# qo-100-relay-controller.net
KiCad netlist of a schematic drawn in EAGLE
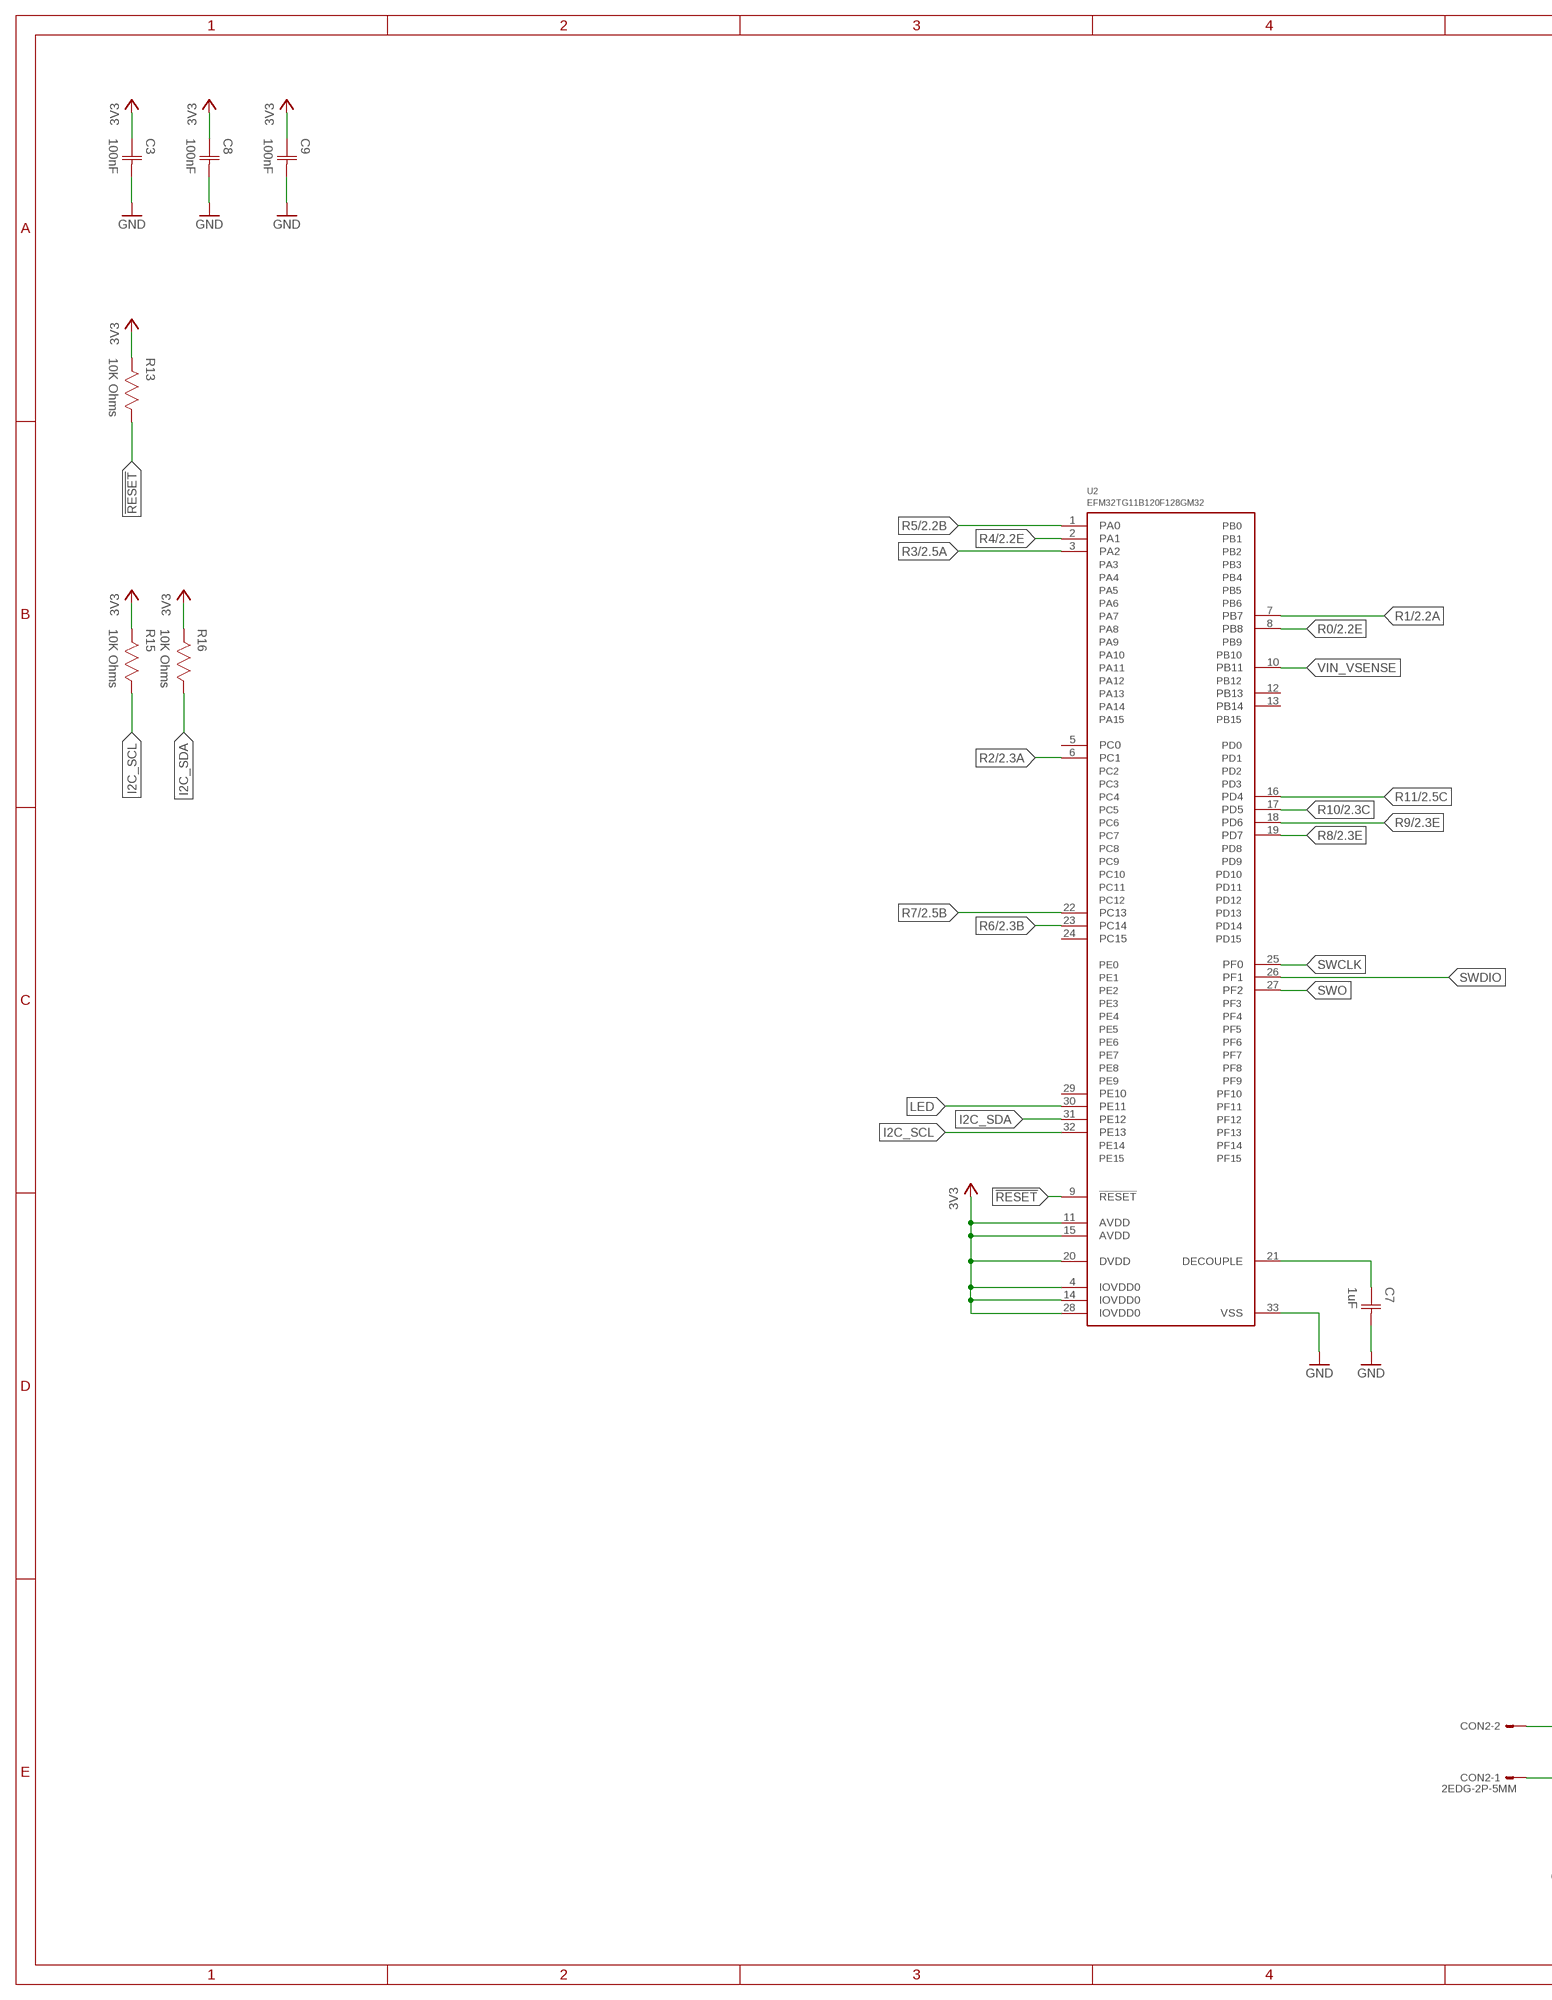
[diagram p0: schematic, sheet 1, part 1 of 2]
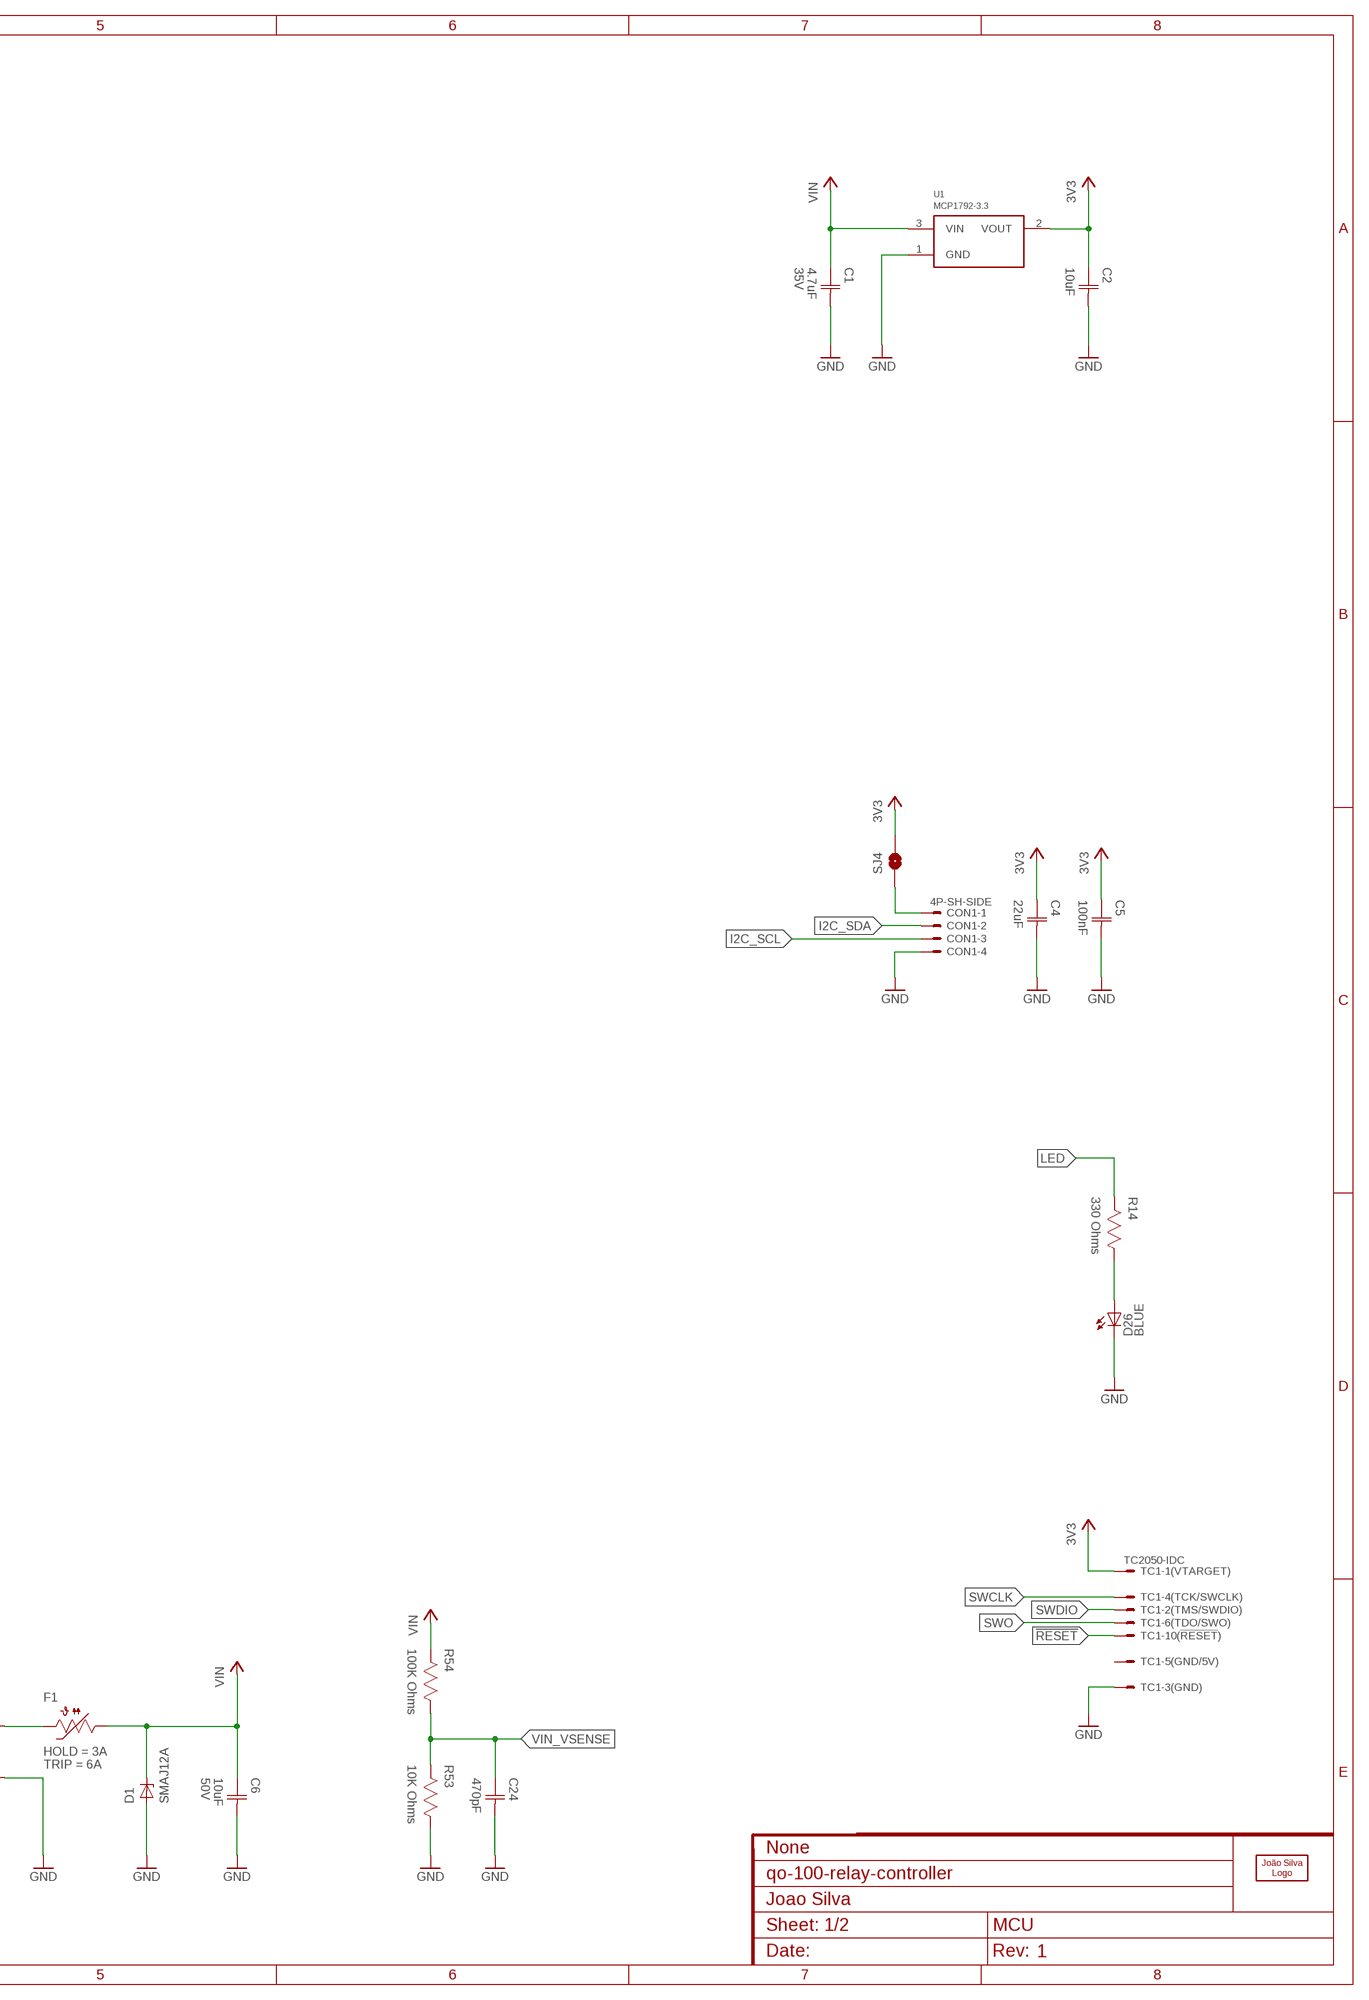
[diagram p1: schematic, sheet 1, part 2 of 2]
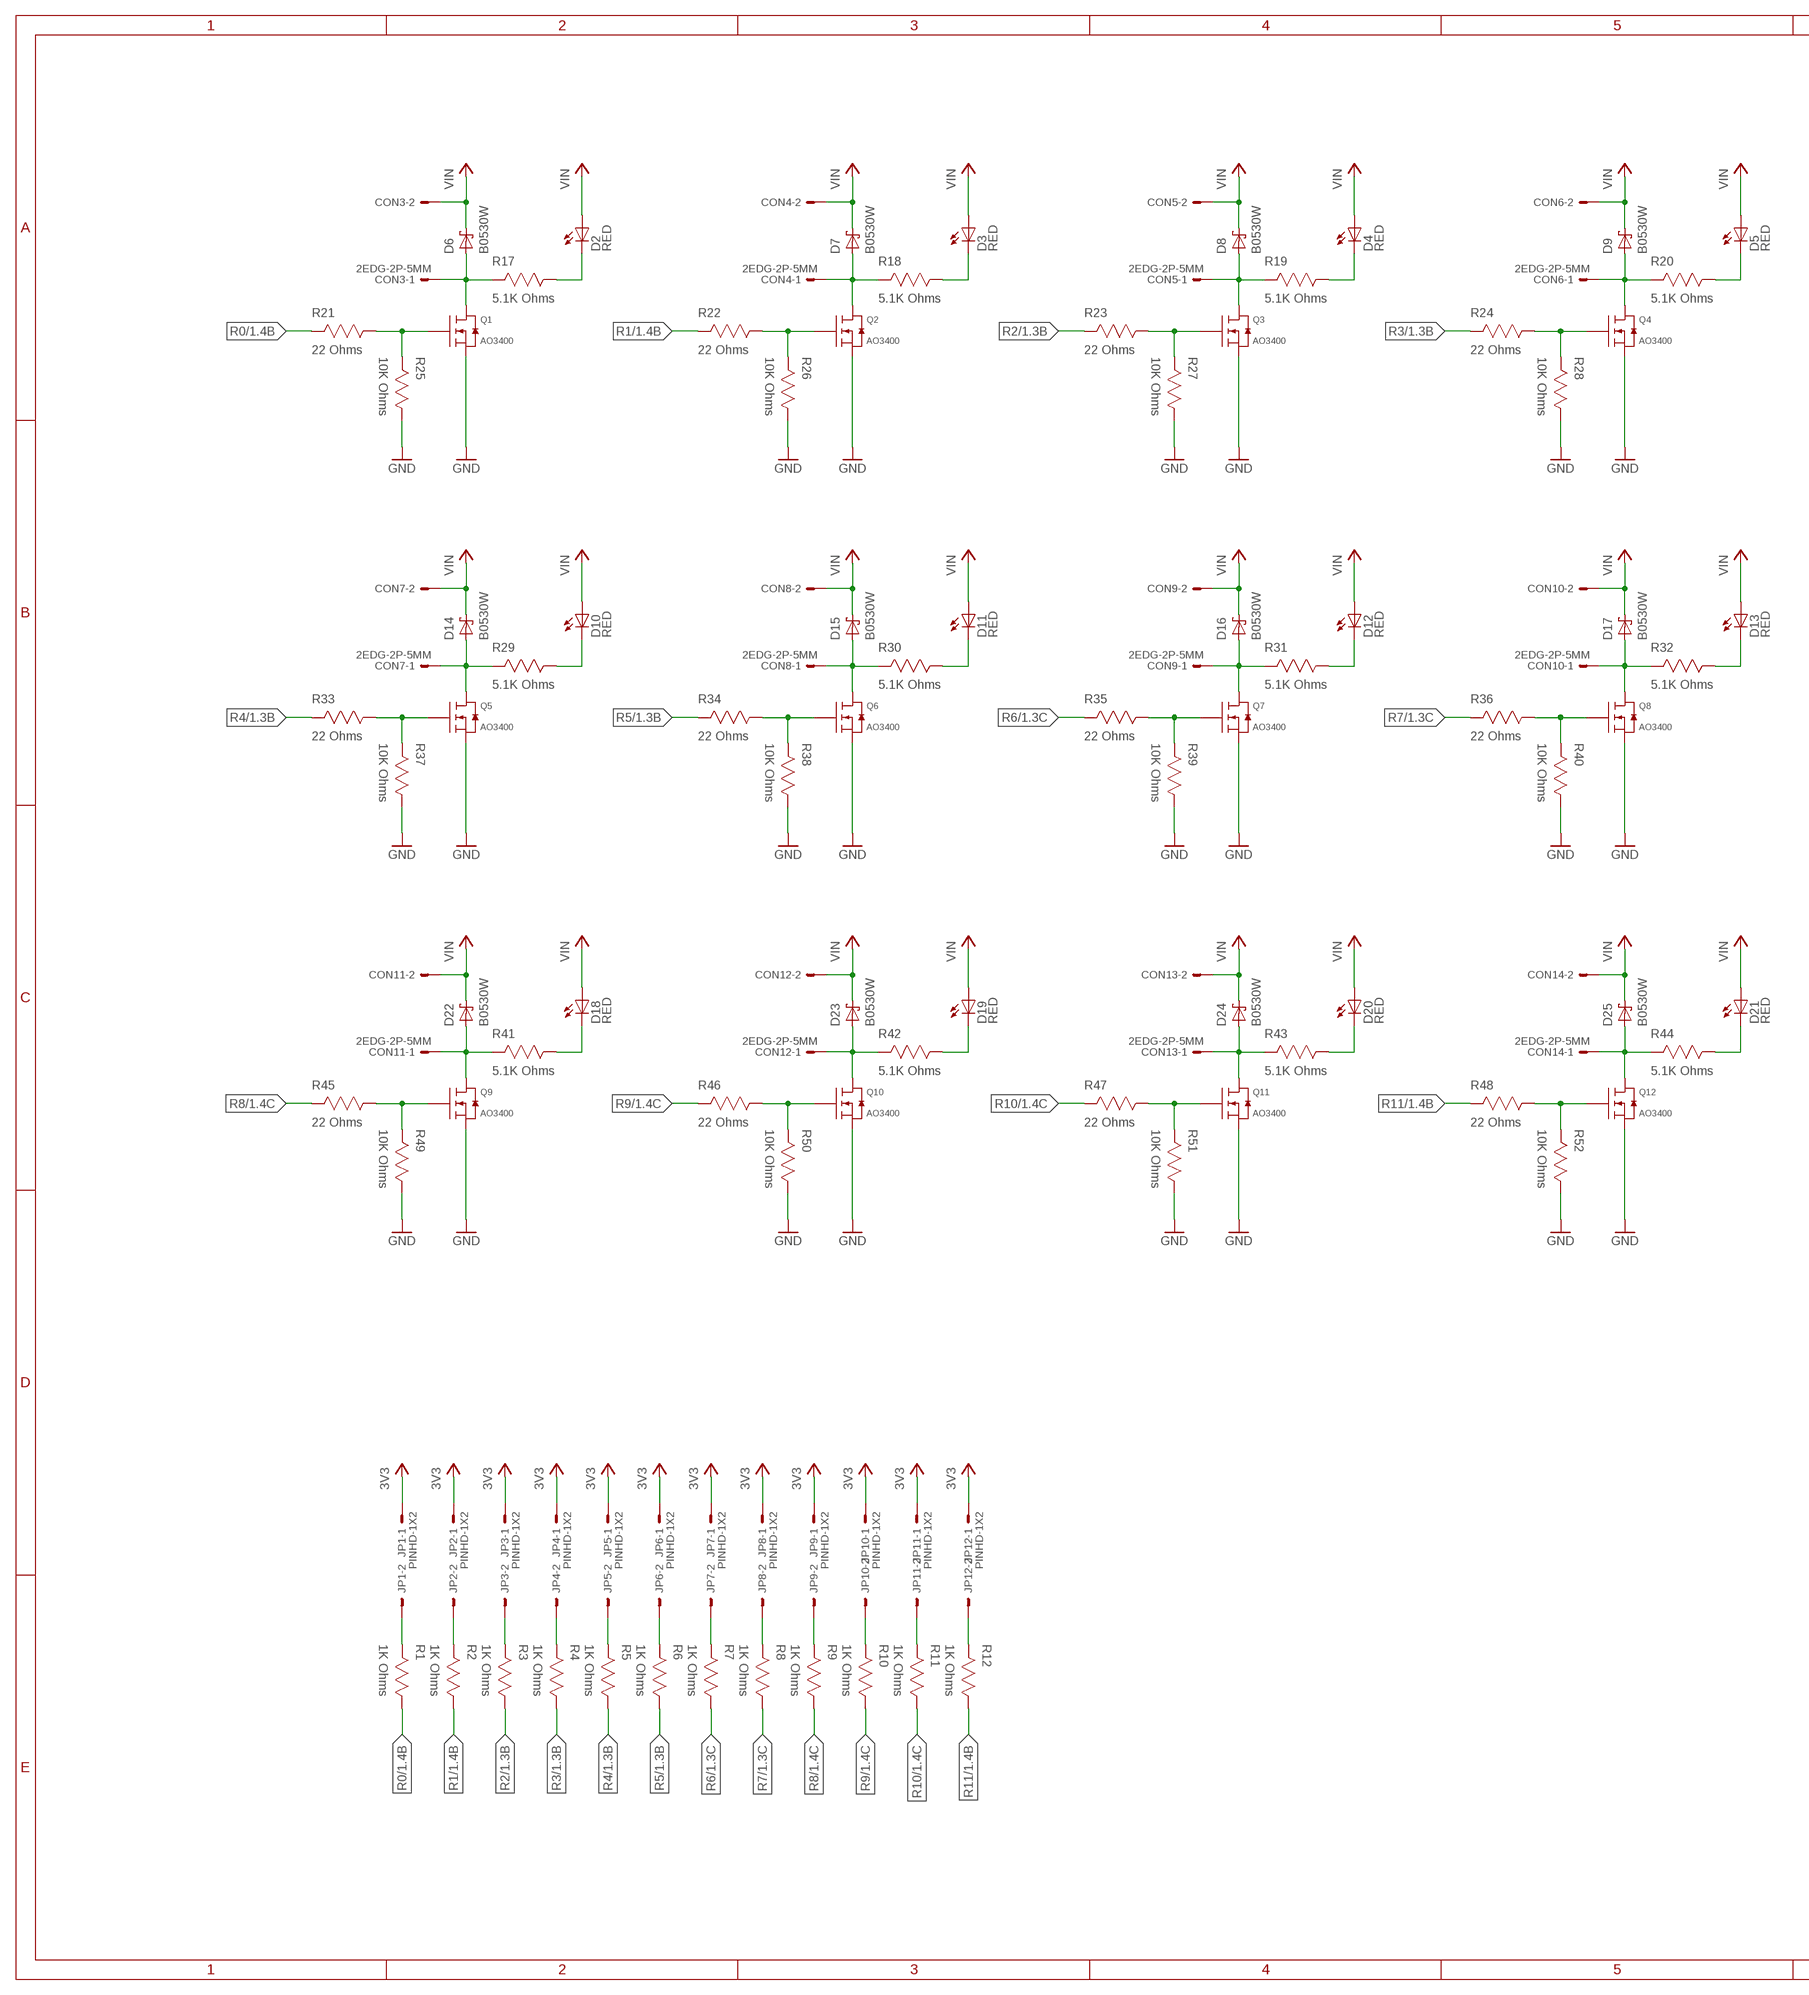
[diagram p2: schematic, sheet 2, part 1 of 2]
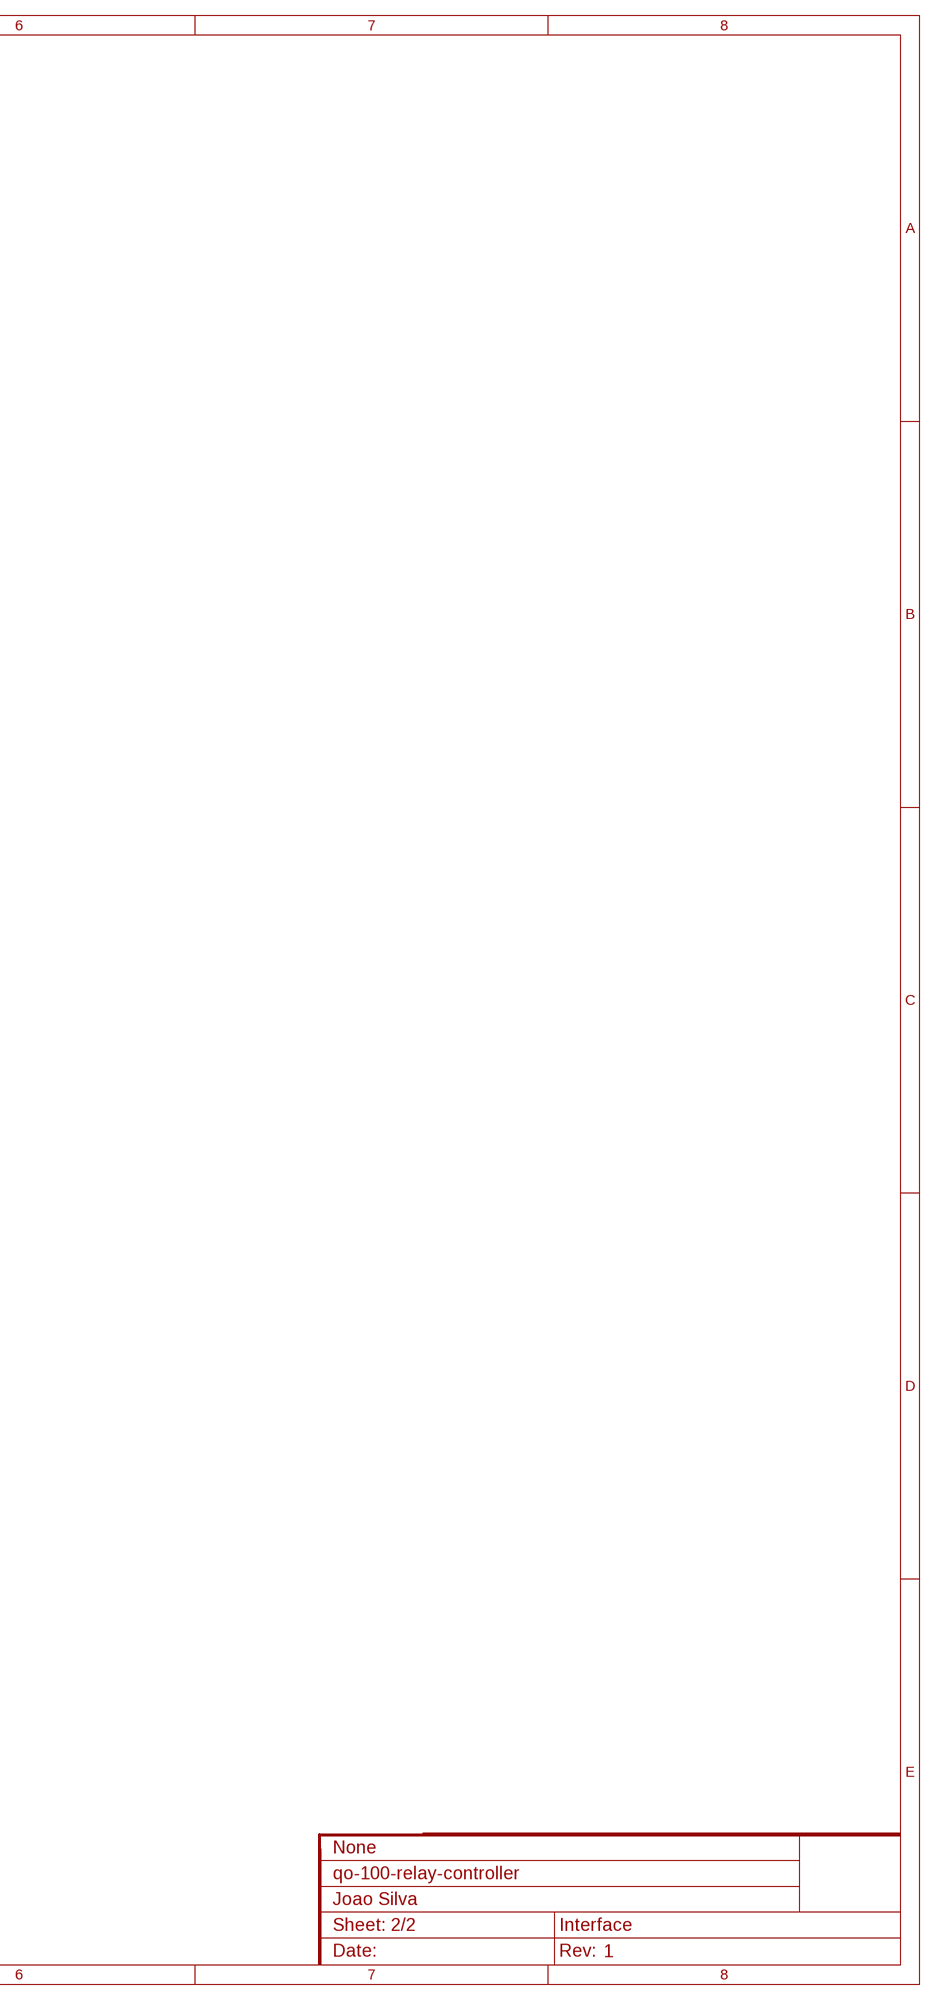
[diagram p3: schematic, sheet 2, part 2 of 2]

(export (version "E")
  (design (tool "Eeschema 10.0.6"))
  (components
    (comp (ref "C1")
      (value "4.7uF")
      (footprint "eagle-import:CAP0603")
      (fields (field (name "VOLTAGE") "35V"))
      (libsource (lib "eagle-import") (part "CAPACITOR-0603"))
    )
    (comp (ref "C2")
      (value "10uF")
      (footprint "eagle-import:CAP0603")
      (libsource (lib "eagle-import") (part "CAPACITOR-0603"))
    )
    (comp (ref "C3")
      (value "100nF")
      (footprint "eagle-import:CAP0603")
      (libsource (lib "eagle-import") (part "CAPACITOR-0603"))
    )
    (comp (ref "C4")
      (value "22uF")
      (footprint "eagle-import:CAP1206")
      (libsource (lib "eagle-import") (part "CAPACITOR-1206"))
    )
    (comp (ref "C5")
      (value "100nF")
      (footprint "eagle-import:CAP0603")
      (libsource (lib "eagle-import") (part "CAPACITOR-0603"))
    )
    (comp (ref "C6")
      (value "10uF")
      (footprint "eagle-import:CAP1206")
      (fields (field (name "VOLTAGE") "50V"))
      (libsource (lib "eagle-import") (part "CAPACITOR-1206"))
    )
    (comp (ref "C7")
      (value "1uF")
      (footprint "eagle-import:CAP0603")
      (libsource (lib "eagle-import") (part "CAPACITOR-0603"))
    )
    (comp (ref "C8")
      (value "100nF")
      (footprint "eagle-import:CAP0603")
      (libsource (lib "eagle-import") (part "CAPACITOR-0603"))
    )
    (comp (ref "C9")
      (value "100nF")
      (footprint "eagle-import:CAP0603")
      (libsource (lib "eagle-import") (part "CAPACITOR-0603"))
    )
    (comp (ref "C24")
      (value "470pF")
      (footprint "eagle-import:CAP0603")
      (libsource (lib "eagle-import") (part "CAPACITOR-0603"))
    )
    (comp (ref "CON1")
      (value "4P-SH-SIDE")
      (footprint "eagle-import:SH-04-SIDE")
      (libsource (lib "eagle-import") (part "4P-SH-SIDE"))
    )
    (comp (ref "CON2")
      (value "2EDG-2P-5MM")
      (footprint "eagle-import:2EDG-2P-5MM")
      (libsource (lib "eagle-import") (part "2EDG-2P-5MM"))
    )
    (comp (ref "D1")
      (value "SMAJ12A")
      (footprint "eagle-import:DO214AC")
      (fields (field (name "MF") "Littelfuse"))
      (libsource (lib "eagle-import") (part "SMAJA12"))
    )
    (comp (ref "D26")
      (value "LED0603")
      (footprint "eagle-import:0603")
      (fields (field (name "COLOR") "BLUE"))
      (libsource (lib "eagle-import") (part "LED0603"))
    )
    (comp (ref "F1")
      (value "2.6A Hold")
      (footprint "eagle-import:1206")
      (fields (field (name "HOLD") "3A") (field (name "TRIP") "6A"))
      (libsource (lib "eagle-import") (part "PTC1206"))
    )
    (comp (ref "LOGO1")
      (value "JS-5MM")
      (footprint "eagle-import:JS_5MM")
      (libsource (lib "eagle-import") (part "JS-5MM"))
    )
    (comp (ref "R13")
      (value "10K Ohms")
      (footprint "eagle-import:RES0603")
      (libsource (lib "eagle-import") (part "RESISTOR-0603"))
    )
    (comp (ref "R14")
      (value "330 Ohms")
      (footprint "eagle-import:RES0603")
      (libsource (lib "eagle-import") (part "RESISTOR-0603"))
    )
    (comp (ref "R15")
      (value "10K Ohms")
      (footprint "eagle-import:RES0603")
      (libsource (lib "eagle-import") (part "RESISTOR-0603"))
    )
    (comp (ref "R16")
      (value "10K Ohms")
      (footprint "eagle-import:RES0603")
      (libsource (lib "eagle-import") (part "RESISTOR-0603"))
    )
    (comp (ref "R53")
      (value "10K Ohms")
      (footprint "eagle-import:RES0603")
      (libsource (lib "eagle-import") (part "RESISTOR-0603"))
    )
    (comp (ref "R54")
      (value "100K Ohms")
      (footprint "eagle-import:RES0603")
      (libsource (lib "eagle-import") (part "RESISTOR-0603"))
    )
    (comp (ref "SJ4")
      (value "SJS")
      (footprint "eagle-import:SJ_S")
      (libsource (lib "eagle-import") (part "SJS"))
    )
    (comp (ref "TC1")
      (value "TC2050-IDC")
      (footprint "eagle-import:TC2050-IDC")
      (libsource (lib "eagle-import") (part "TC2050-IDC"))
    )
    (comp (ref "U1")
      (value "MCP1792-3.3")
      (footprint "eagle-import:SOT23")
      (libsource (lib "eagle-import") (part "MCP1792-3.3"))
    )
    (comp (ref "U2")
      (value "EFM32TG11B120F128GM32")
      (footprint "eagle-import:QFN32_0.5P_TG")
      (libsource (lib "eagle-import") (part "EFM32TG11B1M3220F128G"))
    )
    (comp (ref "CON3")
      (value "2EDG-2P-5MM")
      (footprint "eagle-import:2EDG-2P-5MM")
      (libsource (lib "eagle-import") (part "2EDG-2P-5MM"))
    )
    (comp (ref "CON4")
      (value "2EDG-2P-5MM")
      (footprint "eagle-import:2EDG-2P-5MM")
      (libsource (lib "eagle-import") (part "2EDG-2P-5MM"))
    )
    (comp (ref "CON5")
      (value "2EDG-2P-5MM")
      (footprint "eagle-import:2EDG-2P-5MM")
      (libsource (lib "eagle-import") (part "2EDG-2P-5MM"))
    )
    (comp (ref "CON6")
      (value "2EDG-2P-5MM")
      (footprint "eagle-import:2EDG-2P-5MM")
      (libsource (lib "eagle-import") (part "2EDG-2P-5MM"))
    )
    (comp (ref "CON7")
      (value "2EDG-2P-5MM")
      (footprint "eagle-import:2EDG-2P-5MM")
      (libsource (lib "eagle-import") (part "2EDG-2P-5MM"))
    )
    (comp (ref "CON8")
      (value "2EDG-2P-5MM")
      (footprint "eagle-import:2EDG-2P-5MM")
      (libsource (lib "eagle-import") (part "2EDG-2P-5MM"))
    )
    (comp (ref "CON9")
      (value "2EDG-2P-5MM")
      (footprint "eagle-import:2EDG-2P-5MM")
      (libsource (lib "eagle-import") (part "2EDG-2P-5MM"))
    )
    (comp (ref "CON10")
      (value "2EDG-2P-5MM")
      (footprint "eagle-import:2EDG-2P-5MM")
      (libsource (lib "eagle-import") (part "2EDG-2P-5MM"))
    )
    (comp (ref "CON11")
      (value "2EDG-2P-5MM")
      (footprint "eagle-import:2EDG-2P-5MM")
      (libsource (lib "eagle-import") (part "2EDG-2P-5MM"))
    )
    (comp (ref "CON12")
      (value "2EDG-2P-5MM")
      (footprint "eagle-import:2EDG-2P-5MM")
      (libsource (lib "eagle-import") (part "2EDG-2P-5MM"))
    )
    (comp (ref "CON13")
      (value "2EDG-2P-5MM")
      (footprint "eagle-import:2EDG-2P-5MM")
      (libsource (lib "eagle-import") (part "2EDG-2P-5MM"))
    )
    (comp (ref "CON14")
      (value "2EDG-2P-5MM")
      (footprint "eagle-import:2EDG-2P-5MM")
      (libsource (lib "eagle-import") (part "2EDG-2P-5MM"))
    )
    (comp (ref "D2")
      (value "LED0603")
      (footprint "eagle-import:0603")
      (fields (field (name "COLOR") "RED"))
      (libsource (lib "eagle-import") (part "LED0603"))
    )
    (comp (ref "D3")
      (value "LED0603")
      (footprint "eagle-import:0603")
      (fields (field (name "COLOR") "RED"))
      (libsource (lib "eagle-import") (part "LED0603"))
    )
    (comp (ref "D4")
      (value "LED0603")
      (footprint "eagle-import:0603")
      (fields (field (name "COLOR") "RED"))
      (libsource (lib "eagle-import") (part "LED0603"))
    )
    (comp (ref "D5")
      (value "LED0603")
      (footprint "eagle-import:0603")
      (fields (field (name "COLOR") "RED"))
      (libsource (lib "eagle-import") (part "LED0603"))
    )
    (comp (ref "D6")
      (value "B0530W")
      (footprint "eagle-import:SOD-123")
      (libsource (lib "eagle-import") (part "B0530W"))
    )
    (comp (ref "D7")
      (value "B0530W")
      (footprint "eagle-import:SOD-123")
      (libsource (lib "eagle-import") (part "B0530W"))
    )
    (comp (ref "D8")
      (value "B0530W")
      (footprint "eagle-import:SOD-123")
      (libsource (lib "eagle-import") (part "B0530W"))
    )
    (comp (ref "D9")
      (value "B0530W")
      (footprint "eagle-import:SOD-123")
      (libsource (lib "eagle-import") (part "B0530W"))
    )
    (comp (ref "D10")
      (value "LED0603")
      (footprint "eagle-import:0603")
      (fields (field (name "COLOR") "RED"))
      (libsource (lib "eagle-import") (part "LED0603"))
    )
    (comp (ref "D11")
      (value "LED0603")
      (footprint "eagle-import:0603")
      (fields (field (name "COLOR") "RED"))
      (libsource (lib "eagle-import") (part "LED0603"))
    )
    (comp (ref "D12")
      (value "LED0603")
      (footprint "eagle-import:0603")
      (fields (field (name "COLOR") "RED"))
      (libsource (lib "eagle-import") (part "LED0603"))
    )
    (comp (ref "D13")
      (value "LED0603")
      (footprint "eagle-import:0603")
      (fields (field (name "COLOR") "RED"))
      (libsource (lib "eagle-import") (part "LED0603"))
    )
    (comp (ref "D14")
      (value "B0530W")
      (footprint "eagle-import:SOD-123")
      (libsource (lib "eagle-import") (part "B0530W"))
    )
    (comp (ref "D15")
      (value "B0530W")
      (footprint "eagle-import:SOD-123")
      (libsource (lib "eagle-import") (part "B0530W"))
    )
    (comp (ref "D16")
      (value "B0530W")
      (footprint "eagle-import:SOD-123")
      (libsource (lib "eagle-import") (part "B0530W"))
    )
    (comp (ref "D17")
      (value "B0530W")
      (footprint "eagle-import:SOD-123")
      (libsource (lib "eagle-import") (part "B0530W"))
    )
    (comp (ref "D18")
      (value "LED0603")
      (footprint "eagle-import:0603")
      (fields (field (name "COLOR") "RED"))
      (libsource (lib "eagle-import") (part "LED0603"))
    )
    (comp (ref "D19")
      (value "LED0603")
      (footprint "eagle-import:0603")
      (fields (field (name "COLOR") "RED"))
      (libsource (lib "eagle-import") (part "LED0603"))
    )
    (comp (ref "D20")
      (value "LED0603")
      (footprint "eagle-import:0603")
      (fields (field (name "COLOR") "RED"))
      (libsource (lib "eagle-import") (part "LED0603"))
    )
    (comp (ref "D21")
      (value "LED0603")
      (footprint "eagle-import:0603")
      (fields (field (name "COLOR") "RED"))
      (libsource (lib "eagle-import") (part "LED0603"))
    )
    (comp (ref "D22")
      (value "B0530W")
      (footprint "eagle-import:SOD-123")
      (libsource (lib "eagle-import") (part "B0530W"))
    )
    (comp (ref "D23")
      (value "B0530W")
      (footprint "eagle-import:SOD-123")
      (libsource (lib "eagle-import") (part "B0530W"))
    )
    (comp (ref "D24")
      (value "B0530W")
      (footprint "eagle-import:SOD-123")
      (libsource (lib "eagle-import") (part "B0530W"))
    )
    (comp (ref "D25")
      (value "B0530W")
      (footprint "eagle-import:SOD-123")
      (libsource (lib "eagle-import") (part "B0530W"))
    )
    (comp (ref "JP1")
      (value "PINHD-1X2")
      (footprint "eagle-import:1X02")
      (libsource (lib "eagle-import") (part "PINHD-1X2"))
    )
    (comp (ref "JP2")
      (value "PINHD-1X2")
      (footprint "eagle-import:1X02")
      (libsource (lib "eagle-import") (part "PINHD-1X2"))
    )
    (comp (ref "JP3")
      (value "PINHD-1X2")
      (footprint "eagle-import:1X02")
      (libsource (lib "eagle-import") (part "PINHD-1X2"))
    )
    (comp (ref "JP4")
      (value "PINHD-1X2")
      (footprint "eagle-import:1X02")
      (libsource (lib "eagle-import") (part "PINHD-1X2"))
    )
    (comp (ref "JP5")
      (value "PINHD-1X2")
      (footprint "eagle-import:1X02")
      (libsource (lib "eagle-import") (part "PINHD-1X2"))
    )
    (comp (ref "JP6")
      (value "PINHD-1X2")
      (footprint "eagle-import:1X02")
      (libsource (lib "eagle-import") (part "PINHD-1X2"))
    )
    (comp (ref "JP7")
      (value "PINHD-1X2")
      (footprint "eagle-import:1X02")
      (libsource (lib "eagle-import") (part "PINHD-1X2"))
    )
    (comp (ref "JP8")
      (value "PINHD-1X2")
      (footprint "eagle-import:1X02")
      (libsource (lib "eagle-import") (part "PINHD-1X2"))
    )
    (comp (ref "JP9")
      (value "PINHD-1X2")
      (footprint "eagle-import:1X02")
      (libsource (lib "eagle-import") (part "PINHD-1X2"))
    )
    (comp (ref "JP10")
      (value "PINHD-1X2")
      (footprint "eagle-import:1X02")
      (libsource (lib "eagle-import") (part "PINHD-1X2"))
    )
    (comp (ref "JP11")
      (value "PINHD-1X2")
      (footprint "eagle-import:1X02")
      (libsource (lib "eagle-import") (part "PINHD-1X2"))
    )
    (comp (ref "JP12")
      (value "PINHD-1X2")
      (footprint "eagle-import:1X02")
      (libsource (lib "eagle-import") (part "PINHD-1X2"))
    )
    (comp (ref "Q1")
      (value "AO3400")
      (footprint "eagle-import:SOT23")
      (libsource (lib "eagle-import") (part "AO3400"))
    )
    (comp (ref "Q2")
      (value "AO3400")
      (footprint "eagle-import:SOT23")
      (libsource (lib "eagle-import") (part "AO3400"))
    )
    (comp (ref "Q3")
      (value "AO3400")
      (footprint "eagle-import:SOT23")
      (libsource (lib "eagle-import") (part "AO3400"))
    )
    (comp (ref "Q4")
      (value "AO3400")
      (footprint "eagle-import:SOT23")
      (libsource (lib "eagle-import") (part "AO3400"))
    )
    (comp (ref "Q5")
      (value "AO3400")
      (footprint "eagle-import:SOT23")
      (libsource (lib "eagle-import") (part "AO3400"))
    )
    (comp (ref "Q6")
      (value "AO3400")
      (footprint "eagle-import:SOT23")
      (libsource (lib "eagle-import") (part "AO3400"))
    )
    (comp (ref "Q7")
      (value "AO3400")
      (footprint "eagle-import:SOT23")
      (libsource (lib "eagle-import") (part "AO3400"))
    )
    (comp (ref "Q8")
      (value "AO3400")
      (footprint "eagle-import:SOT23")
      (libsource (lib "eagle-import") (part "AO3400"))
    )
    (comp (ref "Q9")
      (value "AO3400")
      (footprint "eagle-import:SOT23")
      (libsource (lib "eagle-import") (part "AO3400"))
    )
    (comp (ref "Q10")
      (value "AO3400")
      (footprint "eagle-import:SOT23")
      (libsource (lib "eagle-import") (part "AO3400"))
    )
    (comp (ref "Q11")
      (value "AO3400")
      (footprint "eagle-import:SOT23")
      (libsource (lib "eagle-import") (part "AO3400"))
    )
    (comp (ref "Q12")
      (value "AO3400")
      (footprint "eagle-import:SOT23")
      (libsource (lib "eagle-import") (part "AO3400"))
    )
    (comp (ref "R1")
      (value "1K Ohms")
      (footprint "eagle-import:RES0603")
      (libsource (lib "eagle-import") (part "RESISTOR-0603"))
    )
    (comp (ref "R2")
      (value "1K Ohms")
      (footprint "eagle-import:RES0603")
      (libsource (lib "eagle-import") (part "RESISTOR-0603"))
    )
    (comp (ref "R3")
      (value "1K Ohms")
      (footprint "eagle-import:RES0603")
      (libsource (lib "eagle-import") (part "RESISTOR-0603"))
    )
    (comp (ref "R4")
      (value "1K Ohms")
      (footprint "eagle-import:RES0603")
      (libsource (lib "eagle-import") (part "RESISTOR-0603"))
    )
    (comp (ref "R5")
      (value "1K Ohms")
      (footprint "eagle-import:RES0603")
      (libsource (lib "eagle-import") (part "RESISTOR-0603"))
    )
    (comp (ref "R6")
      (value "1K Ohms")
      (footprint "eagle-import:RES0603")
      (libsource (lib "eagle-import") (part "RESISTOR-0603"))
    )
    (comp (ref "R7")
      (value "1K Ohms")
      (footprint "eagle-import:RES0603")
      (libsource (lib "eagle-import") (part "RESISTOR-0603"))
    )
    (comp (ref "R8")
      (value "1K Ohms")
      (footprint "eagle-import:RES0603")
      (libsource (lib "eagle-import") (part "RESISTOR-0603"))
    )
    (comp (ref "R9")
      (value "1K Ohms")
      (footprint "eagle-import:RES0603")
      (libsource (lib "eagle-import") (part "RESISTOR-0603"))
    )
    (comp (ref "R10")
      (value "1K Ohms")
      (footprint "eagle-import:RES0603")
      (libsource (lib "eagle-import") (part "RESISTOR-0603"))
    )
    (comp (ref "R11")
      (value "1K Ohms")
      (footprint "eagle-import:RES0603")
      (libsource (lib "eagle-import") (part "RESISTOR-0603"))
    )
    (comp (ref "R12")
      (value "1K Ohms")
      (footprint "eagle-import:RES0603")
      (libsource (lib "eagle-import") (part "RESISTOR-0603"))
    )
    (comp (ref "R17")
      (value "5.1K Ohms")
      (footprint "eagle-import:RES0603")
      (libsource (lib "eagle-import") (part "RESISTOR-0603"))
    )
    (comp (ref "R18")
      (value "5.1K Ohms")
      (footprint "eagle-import:RES0603")
      (libsource (lib "eagle-import") (part "RESISTOR-0603"))
    )
    (comp (ref "R19")
      (value "5.1K Ohms")
      (footprint "eagle-import:RES0603")
      (libsource (lib "eagle-import") (part "RESISTOR-0603"))
    )
    (comp (ref "R20")
      (value "5.1K Ohms")
      (footprint "eagle-import:RES0603")
      (libsource (lib "eagle-import") (part "RESISTOR-0603"))
    )
    (comp (ref "R21")
      (value "22 Ohms")
      (footprint "eagle-import:RES0603")
      (libsource (lib "eagle-import") (part "RESISTOR-0603"))
    )
    (comp (ref "R22")
      (value "22 Ohms")
      (footprint "eagle-import:RES0603")
      (libsource (lib "eagle-import") (part "RESISTOR-0603"))
    )
    (comp (ref "R23")
      (value "22 Ohms")
      (footprint "eagle-import:RES0603")
      (libsource (lib "eagle-import") (part "RESISTOR-0603"))
    )
    (comp (ref "R24")
      (value "22 Ohms")
      (footprint "eagle-import:RES0603")
      (libsource (lib "eagle-import") (part "RESISTOR-0603"))
    )
    (comp (ref "R25")
      (value "10K Ohms")
      (footprint "eagle-import:RES0603")
      (libsource (lib "eagle-import") (part "RESISTOR-0603"))
    )
    (comp (ref "R26")
      (value "10K Ohms")
      (footprint "eagle-import:RES0603")
      (libsource (lib "eagle-import") (part "RESISTOR-0603"))
    )
    (comp (ref "R27")
      (value "10K Ohms")
      (footprint "eagle-import:RES0603")
      (libsource (lib "eagle-import") (part "RESISTOR-0603"))
    )
    (comp (ref "R28")
      (value "10K Ohms")
      (footprint "eagle-import:RES0603")
      (libsource (lib "eagle-import") (part "RESISTOR-0603"))
    )
    (comp (ref "R29")
      (value "5.1K Ohms")
      (footprint "eagle-import:RES0603")
      (libsource (lib "eagle-import") (part "RESISTOR-0603"))
    )
    (comp (ref "R30")
      (value "5.1K Ohms")
      (footprint "eagle-import:RES0603")
      (libsource (lib "eagle-import") (part "RESISTOR-0603"))
    )
    (comp (ref "R31")
      (value "5.1K Ohms")
      (footprint "eagle-import:RES0603")
      (libsource (lib "eagle-import") (part "RESISTOR-0603"))
    )
    (comp (ref "R32")
      (value "5.1K Ohms")
      (footprint "eagle-import:RES0603")
      (libsource (lib "eagle-import") (part "RESISTOR-0603"))
    )
    (comp (ref "R33")
      (value "22 Ohms")
      (footprint "eagle-import:RES0603")
      (libsource (lib "eagle-import") (part "RESISTOR-0603"))
    )
    (comp (ref "R34")
      (value "22 Ohms")
      (footprint "eagle-import:RES0603")
      (libsource (lib "eagle-import") (part "RESISTOR-0603"))
    )
    (comp (ref "R35")
      (value "22 Ohms")
      (footprint "eagle-import:RES0603")
      (libsource (lib "eagle-import") (part "RESISTOR-0603"))
    )
    (comp (ref "R36")
      (value "22 Ohms")
      (footprint "eagle-import:RES0603")
      (libsource (lib "eagle-import") (part "RESISTOR-0603"))
    )
    (comp (ref "R37")
      (value "10K Ohms")
      (footprint "eagle-import:RES0603")
      (libsource (lib "eagle-import") (part "RESISTOR-0603"))
    )
    (comp (ref "R38")
      (value "10K Ohms")
      (footprint "eagle-import:RES0603")
      (libsource (lib "eagle-import") (part "RESISTOR-0603"))
    )
    (comp (ref "R39")
      (value "10K Ohms")
      (footprint "eagle-import:RES0603")
      (libsource (lib "eagle-import") (part "RESISTOR-0603"))
    )
    (comp (ref "R40")
      (value "10K Ohms")
      (footprint "eagle-import:RES0603")
      (libsource (lib "eagle-import") (part "RESISTOR-0603"))
    )
    (comp (ref "R41")
      (value "5.1K Ohms")
      (footprint "eagle-import:RES0603")
      (libsource (lib "eagle-import") (part "RESISTOR-0603"))
    )
    (comp (ref "R42")
      (value "5.1K Ohms")
      (footprint "eagle-import:RES0603")
      (libsource (lib "eagle-import") (part "RESISTOR-0603"))
    )
    (comp (ref "R43")
      (value "5.1K Ohms")
      (footprint "eagle-import:RES0603")
      (libsource (lib "eagle-import") (part "RESISTOR-0603"))
    )
    (comp (ref "R44")
      (value "5.1K Ohms")
      (footprint "eagle-import:RES0603")
      (libsource (lib "eagle-import") (part "RESISTOR-0603"))
    )
    (comp (ref "R45")
      (value "22 Ohms")
      (footprint "eagle-import:RES0603")
      (libsource (lib "eagle-import") (part "RESISTOR-0603"))
    )
    (comp (ref "R46")
      (value "22 Ohms")
      (footprint "eagle-import:RES0603")
      (libsource (lib "eagle-import") (part "RESISTOR-0603"))
    )
    (comp (ref "R47")
      (value "22 Ohms")
      (footprint "eagle-import:RES0603")
      (libsource (lib "eagle-import") (part "RESISTOR-0603"))
    )
    (comp (ref "R48")
      (value "22 Ohms")
      (footprint "eagle-import:RES0603")
      (libsource (lib "eagle-import") (part "RESISTOR-0603"))
    )
    (comp (ref "R49")
      (value "10K Ohms")
      (footprint "eagle-import:RES0603")
      (libsource (lib "eagle-import") (part "RESISTOR-0603"))
    )
    (comp (ref "R50")
      (value "10K Ohms")
      (footprint "eagle-import:RES0603")
      (libsource (lib "eagle-import") (part "RESISTOR-0603"))
    )
    (comp (ref "R51")
      (value "10K Ohms")
      (footprint "eagle-import:RES0603")
      (libsource (lib "eagle-import") (part "RESISTOR-0603"))
    )
    (comp (ref "R52")
      (value "10K Ohms")
      (footprint "eagle-import:RES0603")
      (libsource (lib "eagle-import") (part "RESISTOR-0603"))
    )
  )
  (nets
    (net (code "1") (name "3V3") (class "Default")
      (node (ref "C2") (pin "1") (pinfunction "C1_1") (pintype "passive"))
      (node (ref "C3") (pin "1") (pinfunction "C1_1") (pintype "passive"))
      (node (ref "C4") (pin "1") (pinfunction "C1_1") (pintype "passive"))
      (node (ref "C5") (pin "1") (pinfunction "C1_1") (pintype "passive"))
      (node (ref "C8") (pin "1") (pinfunction "C1_1") (pintype "passive"))
      (node (ref "C9") (pin "1") (pinfunction "C1_1") (pintype "passive"))
      (node (ref "JP1") (pin "1") (pinfunction "S_1") (pintype "passive"))
      (node (ref "JP10") (pin "1") (pinfunction "S_1") (pintype "passive"))
      (node (ref "JP11") (pin "1") (pinfunction "S_1") (pintype "passive"))
      (node (ref "JP12") (pin "1") (pinfunction "S_1") (pintype "passive"))
      (node (ref "JP2") (pin "1") (pinfunction "S_1") (pintype "passive"))
      (node (ref "JP3") (pin "1") (pinfunction "S_1") (pintype "passive"))
      (node (ref "JP4") (pin "1") (pinfunction "S_1") (pintype "passive"))
      (node (ref "JP5") (pin "1") (pinfunction "S_1") (pintype "passive"))
      (node (ref "JP6") (pin "1") (pinfunction "S_1") (pintype "passive"))
      (node (ref "JP7") (pin "1") (pinfunction "S_1") (pintype "passive"))
      (node (ref "JP8") (pin "1") (pinfunction "S_1") (pintype "passive"))
      (node (ref "JP9") (pin "1") (pinfunction "S_1") (pintype "passive"))
      (node (ref "R13") (pin "2") (pinfunction "2_2") (pintype "passive"))
      (node (ref "R15") (pin "2") (pinfunction "2_2") (pintype "passive"))
      (node (ref "R16") (pin "2") (pinfunction "2_2") (pintype "passive"))
      (node (ref "SJ4") (pin "2") (pinfunction "2_2") (pintype "passive"))
      (node (ref "TC1") (pin "1") (pinfunction "S_1") (pintype "passive"))
      (node (ref "U1") (pin "2") (pinfunction "VOUT_2") (pintype "bidirectional"))
      (node (ref "U2") (pin "11") (pinfunction "AVDD_11") (pintype "bidirectional"))
      (node (ref "U2") (pin "14") (pinfunction "IOVDD0_14") (pintype "bidirectional"))
      (node (ref "U2") (pin "15") (pinfunction "AVDD_15") (pintype "bidirectional"))
      (node (ref "U2") (pin "20") (pinfunction "DVDD_20") (pintype "bidirectional"))
      (node (ref "U2") (pin "28") (pinfunction "IOVDD0_28") (pintype "bidirectional"))
      (node (ref "U2") (pin "4") (pinfunction "IOVDD0_4") (pintype "bidirectional"))
    )
    (net (code "2") (name "GND") (class "Default")
      (node (ref "C1") (pin "2") (pinfunction "C2_2") (pintype "passive"))
      (node (ref "C2") (pin "2") (pinfunction "C2_2") (pintype "passive"))
      (node (ref "C24") (pin "2") (pinfunction "C2_2") (pintype "passive"))
      (node (ref "C3") (pin "2") (pinfunction "C2_2") (pintype "passive"))
      (node (ref "C4") (pin "2") (pinfunction "C2_2") (pintype "passive"))
      (node (ref "C5") (pin "2") (pinfunction "C2_2") (pintype "passive"))
      (node (ref "C6") (pin "2") (pinfunction "C2_2") (pintype "passive"))
      (node (ref "C7") (pin "2") (pinfunction "C2_2") (pintype "passive"))
      (node (ref "C8") (pin "2") (pinfunction "C2_2") (pintype "passive"))
      (node (ref "C9") (pin "2") (pinfunction "C2_2") (pintype "passive"))
      (node (ref "CON1") (pin "4") (pinfunction "S_4") (pintype "passive"))
      (node (ref "CON2") (pin "P$1") (pinfunction "S_P$1") (pintype "passive"))
      (node (ref "D1") (pin "A") (pinfunction "A_A") (pintype "passive"))
      (node (ref "D26") (pin "C") (pinfunction "C_C") (pintype "passive"))
      (node (ref "Q1") (pin "2") (pinfunction "S_2") (pintype "passive"))
      (node (ref "Q10") (pin "2") (pinfunction "S_2") (pintype "passive"))
      (node (ref "Q11") (pin "2") (pinfunction "S_2") (pintype "passive"))
      (node (ref "Q12") (pin "2") (pinfunction "S_2") (pintype "passive"))
      (node (ref "Q2") (pin "2") (pinfunction "S_2") (pintype "passive"))
      (node (ref "Q3") (pin "2") (pinfunction "S_2") (pintype "passive"))
      (node (ref "Q4") (pin "2") (pinfunction "S_2") (pintype "passive"))
      (node (ref "Q5") (pin "2") (pinfunction "S_2") (pintype "passive"))
      (node (ref "Q6") (pin "2") (pinfunction "S_2") (pintype "passive"))
      (node (ref "Q7") (pin "2") (pinfunction "S_2") (pintype "passive"))
      (node (ref "Q8") (pin "2") (pinfunction "S_2") (pintype "passive"))
      (node (ref "Q9") (pin "2") (pinfunction "S_2") (pintype "passive"))
      (node (ref "R25") (pin "1") (pinfunction "1_1") (pintype "passive"))
      (node (ref "R26") (pin "1") (pinfunction "1_1") (pintype "passive"))
      (node (ref "R27") (pin "1") (pinfunction "1_1") (pintype "passive"))
      (node (ref "R28") (pin "1") (pinfunction "1_1") (pintype "passive"))
      (node (ref "R37") (pin "1") (pinfunction "1_1") (pintype "passive"))
      (node (ref "R38") (pin "1") (pinfunction "1_1") (pintype "passive"))
      (node (ref "R39") (pin "1") (pinfunction "1_1") (pintype "passive"))
      (node (ref "R40") (pin "1") (pinfunction "1_1") (pintype "passive"))
      (node (ref "R49") (pin "1") (pinfunction "1_1") (pintype "passive"))
      (node (ref "R50") (pin "1") (pinfunction "1_1") (pintype "passive"))
      (node (ref "R51") (pin "1") (pinfunction "1_1") (pintype "passive"))
      (node (ref "R52") (pin "1") (pinfunction "1_1") (pintype "passive"))
      (node (ref "R53") (pin "1") (pinfunction "1_1") (pintype "passive"))
      (node (ref "TC1") (pin "3") (pinfunction "S_3") (pintype "passive"))
      (node (ref "U1") (pin "1") (pinfunction "GND_1") (pintype "bidirectional"))
      (node (ref "U2") (pin "33") (pinfunction "VSS_33") (pintype "bidirectional"))
    )
    (net (code "3") (name "I2C_SCL") (class "Default")
      (node (ref "CON1") (pin "3") (pinfunction "S_3") (pintype "passive"))
      (node (ref "R15") (pin "1") (pinfunction "1_1") (pintype "passive"))
      (node (ref "U2") (pin "32") (pinfunction "PE13_32") (pintype "bidirectional"))
    )
    (net (code "4") (name "I2C_SDA") (class "Default")
      (node (ref "CON1") (pin "2") (pinfunction "S_2") (pintype "passive"))
      (node (ref "R16") (pin "1") (pinfunction "1_1") (pintype "passive"))
      (node (ref "U2") (pin "31") (pinfunction "PE12_31") (pintype "bidirectional"))
    )
    (net (code "5") (name "LED") (class "Default")
      (node (ref "R14") (pin "2") (pinfunction "2_2") (pintype "passive"))
      (node (ref "U2") (pin "30") (pinfunction "PE11_30") (pintype "bidirectional"))
    )
    (net (code "6") (name "Net-(C7-C1)") (class "Default")
      (node (ref "C7") (pin "1") (pinfunction "C1_1") (pintype "passive"))
      (node (ref "U2") (pin "21") (pinfunction "DECOUPLE_21") (pintype "bidirectional"))
    )
    (net (code "7") (name "Net-(CON1A-S)") (class "Default")
      (node (ref "CON1") (pin "1") (pinfunction "S_1") (pintype "passive"))
      (node (ref "SJ4") (pin "1") (pinfunction "1_1") (pintype "passive"))
    )
    (net (code "8") (name "Net-(CON2B-S)") (class "Default")
      (node (ref "CON2") (pin "P$2") (pinfunction "S_P$2") (pintype "passive"))
      (node (ref "F1") (pin "2") (pinfunction "2_2") (pintype "passive"))
    )
    (net (code "9") (name "Net-(CON3A-S)") (class "Default")
      (node (ref "CON3") (pin "P$1") (pinfunction "S_P$1") (pintype "passive"))
      (node (ref "D6") (pin "A") (pinfunction "A_A") (pintype "passive"))
      (node (ref "Q1") (pin "3") (pinfunction "D_3") (pintype "passive"))
      (node (ref "R17") (pin "2") (pinfunction "2_2") (pintype "passive"))
    )
    (net (code "10") (name "Net-(CON4A-S)") (class "Default")
      (node (ref "CON4") (pin "P$1") (pinfunction "S_P$1") (pintype "passive"))
      (node (ref "D7") (pin "A") (pinfunction "A_A") (pintype "passive"))
      (node (ref "Q2") (pin "3") (pinfunction "D_3") (pintype "passive"))
      (node (ref "R18") (pin "2") (pinfunction "2_2") (pintype "passive"))
    )
    (net (code "11") (name "Net-(CON5A-S)") (class "Default")
      (node (ref "CON5") (pin "P$1") (pinfunction "S_P$1") (pintype "passive"))
      (node (ref "D8") (pin "A") (pinfunction "A_A") (pintype "passive"))
      (node (ref "Q3") (pin "3") (pinfunction "D_3") (pintype "passive"))
      (node (ref "R19") (pin "2") (pinfunction "2_2") (pintype "passive"))
    )
    (net (code "12") (name "Net-(CON6A-S)") (class "Default")
      (node (ref "CON6") (pin "P$1") (pinfunction "S_P$1") (pintype "passive"))
      (node (ref "D9") (pin "A") (pinfunction "A_A") (pintype "passive"))
      (node (ref "Q4") (pin "3") (pinfunction "D_3") (pintype "passive"))
      (node (ref "R20") (pin "2") (pinfunction "2_2") (pintype "passive"))
    )
    (net (code "13") (name "Net-(CON7A-S)") (class "Default")
      (node (ref "CON7") (pin "P$1") (pinfunction "S_P$1") (pintype "passive"))
      (node (ref "D14") (pin "A") (pinfunction "A_A") (pintype "passive"))
      (node (ref "Q5") (pin "3") (pinfunction "D_3") (pintype "passive"))
      (node (ref "R29") (pin "2") (pinfunction "2_2") (pintype "passive"))
    )
    (net (code "14") (name "Net-(CON8A-S)") (class "Default")
      (node (ref "CON8") (pin "P$1") (pinfunction "S_P$1") (pintype "passive"))
      (node (ref "D15") (pin "A") (pinfunction "A_A") (pintype "passive"))
      (node (ref "Q6") (pin "3") (pinfunction "D_3") (pintype "passive"))
      (node (ref "R30") (pin "2") (pinfunction "2_2") (pintype "passive"))
    )
    (net (code "15") (name "Net-(CON9A-S)") (class "Default")
      (node (ref "CON9") (pin "P$1") (pinfunction "S_P$1") (pintype "passive"))
      (node (ref "D16") (pin "A") (pinfunction "A_A") (pintype "passive"))
      (node (ref "Q7") (pin "3") (pinfunction "D_3") (pintype "passive"))
      (node (ref "R31") (pin "2") (pinfunction "2_2") (pintype "passive"))
    )
    (net (code "16") (name "Net-(CON10A-S)") (class "Default")
      (node (ref "CON10") (pin "P$1") (pinfunction "S_P$1") (pintype "passive"))
      (node (ref "D17") (pin "A") (pinfunction "A_A") (pintype "passive"))
      (node (ref "Q8") (pin "3") (pinfunction "D_3") (pintype "passive"))
      (node (ref "R32") (pin "2") (pinfunction "2_2") (pintype "passive"))
    )
    (net (code "17") (name "Net-(CON11A-S)") (class "Default")
      (node (ref "CON11") (pin "P$1") (pinfunction "S_P$1") (pintype "passive"))
      (node (ref "D22") (pin "A") (pinfunction "A_A") (pintype "passive"))
      (node (ref "Q9") (pin "3") (pinfunction "D_3") (pintype "passive"))
      (node (ref "R41") (pin "2") (pinfunction "2_2") (pintype "passive"))
    )
    (net (code "18") (name "Net-(CON12A-S)") (class "Default")
      (node (ref "CON12") (pin "P$1") (pinfunction "S_P$1") (pintype "passive"))
      (node (ref "D23") (pin "A") (pinfunction "A_A") (pintype "passive"))
      (node (ref "Q10") (pin "3") (pinfunction "D_3") (pintype "passive"))
      (node (ref "R42") (pin "2") (pinfunction "2_2") (pintype "passive"))
    )
    (net (code "19") (name "Net-(CON13A-S)") (class "Default")
      (node (ref "CON13") (pin "P$1") (pinfunction "S_P$1") (pintype "passive"))
      (node (ref "D24") (pin "A") (pinfunction "A_A") (pintype "passive"))
      (node (ref "Q11") (pin "3") (pinfunction "D_3") (pintype "passive"))
      (node (ref "R43") (pin "2") (pinfunction "2_2") (pintype "passive"))
    )
    (net (code "20") (name "Net-(CON14A-S)") (class "Default")
      (node (ref "CON14") (pin "P$1") (pinfunction "S_P$1") (pintype "passive"))
      (node (ref "D25") (pin "A") (pinfunction "A_A") (pintype "passive"))
      (node (ref "Q12") (pin "3") (pinfunction "D_3") (pintype "passive"))
      (node (ref "R44") (pin "2") (pinfunction "2_2") (pintype "passive"))
    )
    (net (code "21") (name "Net-(D2-PadC)") (class "Default")
      (node (ref "D2") (pin "C") (pinfunction "C_C") (pintype "passive"))
      (node (ref "R17") (pin "1") (pinfunction "1_1") (pintype "passive"))
    )
    (net (code "22") (name "Net-(D3-PadC)") (class "Default")
      (node (ref "D3") (pin "C") (pinfunction "C_C") (pintype "passive"))
      (node (ref "R18") (pin "1") (pinfunction "1_1") (pintype "passive"))
    )
    (net (code "23") (name "Net-(D4-PadC)") (class "Default")
      (node (ref "D4") (pin "C") (pinfunction "C_C") (pintype "passive"))
      (node (ref "R19") (pin "1") (pinfunction "1_1") (pintype "passive"))
    )
    (net (code "24") (name "Net-(D5-PadC)") (class "Default")
      (node (ref "D5") (pin "C") (pinfunction "C_C") (pintype "passive"))
      (node (ref "R20") (pin "1") (pinfunction "1_1") (pintype "passive"))
    )
    (net (code "25") (name "Net-(D10-PadC)") (class "Default")
      (node (ref "D10") (pin "C") (pinfunction "C_C") (pintype "passive"))
      (node (ref "R29") (pin "1") (pinfunction "1_1") (pintype "passive"))
    )
    (net (code "26") (name "Net-(D11-PadC)") (class "Default")
      (node (ref "D11") (pin "C") (pinfunction "C_C") (pintype "passive"))
      (node (ref "R30") (pin "1") (pinfunction "1_1") (pintype "passive"))
    )
    (net (code "27") (name "Net-(D12-PadC)") (class "Default")
      (node (ref "D12") (pin "C") (pinfunction "C_C") (pintype "passive"))
      (node (ref "R31") (pin "1") (pinfunction "1_1") (pintype "passive"))
    )
    (net (code "28") (name "Net-(D13-PadC)") (class "Default")
      (node (ref "D13") (pin "C") (pinfunction "C_C") (pintype "passive"))
      (node (ref "R32") (pin "1") (pinfunction "1_1") (pintype "passive"))
    )
    (net (code "29") (name "Net-(D18-PadC)") (class "Default")
      (node (ref "D18") (pin "C") (pinfunction "C_C") (pintype "passive"))
      (node (ref "R41") (pin "1") (pinfunction "1_1") (pintype "passive"))
    )
    (net (code "30") (name "Net-(D19-PadC)") (class "Default")
      (node (ref "D19") (pin "C") (pinfunction "C_C") (pintype "passive"))
      (node (ref "R42") (pin "1") (pinfunction "1_1") (pintype "passive"))
    )
    (net (code "31") (name "Net-(D20-PadC)") (class "Default")
      (node (ref "D20") (pin "C") (pinfunction "C_C") (pintype "passive"))
      (node (ref "R43") (pin "1") (pinfunction "1_1") (pintype "passive"))
    )
    (net (code "32") (name "Net-(D21-PadC)") (class "Default")
      (node (ref "D21") (pin "C") (pinfunction "C_C") (pintype "passive"))
      (node (ref "R44") (pin "1") (pinfunction "1_1") (pintype "passive"))
    )
    (net (code "33") (name "Net-(D26-PadA)") (class "Default")
      (node (ref "D26") (pin "A") (pinfunction "A_A") (pintype "passive"))
      (node (ref "R14") (pin "1") (pinfunction "1_1") (pintype "passive"))
    )
    (net (code "34") (name "Net-(JP1B-S)") (class "Default")
      (node (ref "JP1") (pin "2") (pinfunction "S_2") (pintype "passive"))
      (node (ref "R1") (pin "2") (pinfunction "2_2") (pintype "passive"))
    )
    (net (code "35") (name "Net-(JP2B-S)") (class "Default")
      (node (ref "JP2") (pin "2") (pinfunction "S_2") (pintype "passive"))
      (node (ref "R2") (pin "2") (pinfunction "2_2") (pintype "passive"))
    )
    (net (code "36") (name "Net-(JP3B-S)") (class "Default")
      (node (ref "JP3") (pin "2") (pinfunction "S_2") (pintype "passive"))
      (node (ref "R3") (pin "2") (pinfunction "2_2") (pintype "passive"))
    )
    (net (code "37") (name "Net-(JP4B-S)") (class "Default")
      (node (ref "JP4") (pin "2") (pinfunction "S_2") (pintype "passive"))
      (node (ref "R4") (pin "2") (pinfunction "2_2") (pintype "passive"))
    )
    (net (code "38") (name "Net-(JP5B-S)") (class "Default")
      (node (ref "JP5") (pin "2") (pinfunction "S_2") (pintype "passive"))
      (node (ref "R5") (pin "2") (pinfunction "2_2") (pintype "passive"))
    )
    (net (code "39") (name "Net-(JP6B-S)") (class "Default")
      (node (ref "JP6") (pin "2") (pinfunction "S_2") (pintype "passive"))
      (node (ref "R6") (pin "2") (pinfunction "2_2") (pintype "passive"))
    )
    (net (code "40") (name "Net-(JP7B-S)") (class "Default")
      (node (ref "JP7") (pin "2") (pinfunction "S_2") (pintype "passive"))
      (node (ref "R7") (pin "2") (pinfunction "2_2") (pintype "passive"))
    )
    (net (code "41") (name "Net-(JP8B-S)") (class "Default")
      (node (ref "JP8") (pin "2") (pinfunction "S_2") (pintype "passive"))
      (node (ref "R8") (pin "2") (pinfunction "2_2") (pintype "passive"))
    )
    (net (code "42") (name "Net-(JP9B-S)") (class "Default")
      (node (ref "JP9") (pin "2") (pinfunction "S_2") (pintype "passive"))
      (node (ref "R9") (pin "2") (pinfunction "2_2") (pintype "passive"))
    )
    (net (code "43") (name "Net-(JP10B-S)") (class "Default")
      (node (ref "JP10") (pin "2") (pinfunction "S_2") (pintype "passive"))
      (node (ref "R10") (pin "2") (pinfunction "2_2") (pintype "passive"))
    )
    (net (code "44") (name "Net-(JP11B-S)") (class "Default")
      (node (ref "JP11") (pin "2") (pinfunction "S_2") (pintype "passive"))
      (node (ref "R11") (pin "2") (pinfunction "2_2") (pintype "passive"))
    )
    (net (code "45") (name "Net-(JP12B-S)") (class "Default")
      (node (ref "JP12") (pin "2") (pinfunction "S_2") (pintype "passive"))
      (node (ref "R12") (pin "2") (pinfunction "2_2") (pintype "passive"))
    )
    (net (code "46") (name "Net-(Q1-G)") (class "Default")
      (node (ref "Q1") (pin "1") (pinfunction "G_1") (pintype "passive"))
      (node (ref "R21") (pin "1") (pinfunction "1_1") (pintype "passive"))
      (node (ref "R25") (pin "2") (pinfunction "2_2") (pintype "passive"))
    )
    (net (code "47") (name "Net-(Q2-G)") (class "Default")
      (node (ref "Q2") (pin "1") (pinfunction "G_1") (pintype "passive"))
      (node (ref "R22") (pin "1") (pinfunction "1_1") (pintype "passive"))
      (node (ref "R26") (pin "2") (pinfunction "2_2") (pintype "passive"))
    )
    (net (code "48") (name "Net-(Q3-G)") (class "Default")
      (node (ref "Q3") (pin "1") (pinfunction "G_1") (pintype "passive"))
      (node (ref "R23") (pin "1") (pinfunction "1_1") (pintype "passive"))
      (node (ref "R27") (pin "2") (pinfunction "2_2") (pintype "passive"))
    )
    (net (code "49") (name "Net-(Q4-G)") (class "Default")
      (node (ref "Q4") (pin "1") (pinfunction "G_1") (pintype "passive"))
      (node (ref "R24") (pin "1") (pinfunction "1_1") (pintype "passive"))
      (node (ref "R28") (pin "2") (pinfunction "2_2") (pintype "passive"))
    )
    (net (code "50") (name "Net-(Q5-G)") (class "Default")
      (node (ref "Q5") (pin "1") (pinfunction "G_1") (pintype "passive"))
      (node (ref "R33") (pin "1") (pinfunction "1_1") (pintype "passive"))
      (node (ref "R37") (pin "2") (pinfunction "2_2") (pintype "passive"))
    )
    (net (code "51") (name "Net-(Q6-G)") (class "Default")
      (node (ref "Q6") (pin "1") (pinfunction "G_1") (pintype "passive"))
      (node (ref "R34") (pin "1") (pinfunction "1_1") (pintype "passive"))
      (node (ref "R38") (pin "2") (pinfunction "2_2") (pintype "passive"))
    )
    (net (code "52") (name "Net-(Q7-G)") (class "Default")
      (node (ref "Q7") (pin "1") (pinfunction "G_1") (pintype "passive"))
      (node (ref "R35") (pin "1") (pinfunction "1_1") (pintype "passive"))
      (node (ref "R39") (pin "2") (pinfunction "2_2") (pintype "passive"))
    )
    (net (code "53") (name "Net-(Q8-G)") (class "Default")
      (node (ref "Q8") (pin "1") (pinfunction "G_1") (pintype "passive"))
      (node (ref "R36") (pin "1") (pinfunction "1_1") (pintype "passive"))
      (node (ref "R40") (pin "2") (pinfunction "2_2") (pintype "passive"))
    )
    (net (code "54") (name "Net-(Q9-G)") (class "Default")
      (node (ref "Q9") (pin "1") (pinfunction "G_1") (pintype "passive"))
      (node (ref "R45") (pin "1") (pinfunction "1_1") (pintype "passive"))
      (node (ref "R49") (pin "2") (pinfunction "2_2") (pintype "passive"))
    )
    (net (code "55") (name "Net-(Q10-G)") (class "Default")
      (node (ref "Q10") (pin "1") (pinfunction "G_1") (pintype "passive"))
      (node (ref "R46") (pin "1") (pinfunction "1_1") (pintype "passive"))
      (node (ref "R50") (pin "2") (pinfunction "2_2") (pintype "passive"))
    )
    (net (code "56") (name "Net-(Q11-G)") (class "Default")
      (node (ref "Q11") (pin "1") (pinfunction "G_1") (pintype "passive"))
      (node (ref "R47") (pin "1") (pinfunction "1_1") (pintype "passive"))
      (node (ref "R51") (pin "2") (pinfunction "2_2") (pintype "passive"))
    )
    (net (code "57") (name "Net-(Q12-G)") (class "Default")
      (node (ref "Q12") (pin "1") (pinfunction "G_1") (pintype "passive"))
      (node (ref "R48") (pin "1") (pinfunction "1_1") (pintype "passive"))
      (node (ref "R52") (pin "2") (pinfunction "2_2") (pintype "passive"))
    )
    (net (code "58") (name "R0") (class "Default")
      (node (ref "R1") (pin "1") (pinfunction "1_1") (pintype "passive"))
      (node (ref "R21") (pin "2") (pinfunction "2_2") (pintype "passive"))
      (node (ref "U2") (pin "8") (pinfunction "PB8_8") (pintype "bidirectional"))
    )
    (net (code "59") (name "R1") (class "Default")
      (node (ref "R2") (pin "1") (pinfunction "1_1") (pintype "passive"))
      (node (ref "R22") (pin "2") (pinfunction "2_2") (pintype "passive"))
      (node (ref "U2") (pin "7") (pinfunction "PB7_7") (pintype "bidirectional"))
    )
    (net (code "60") (name "R2") (class "Default")
      (node (ref "R23") (pin "2") (pinfunction "2_2") (pintype "passive"))
      (node (ref "R3") (pin "1") (pinfunction "1_1") (pintype "passive"))
      (node (ref "U2") (pin "6") (pinfunction "PC1_6") (pintype "bidirectional"))
    )
    (net (code "61") (name "R3") (class "Default")
      (node (ref "R24") (pin "2") (pinfunction "2_2") (pintype "passive"))
      (node (ref "R4") (pin "1") (pinfunction "1_1") (pintype "passive"))
      (node (ref "U2") (pin "3") (pinfunction "PA2_3") (pintype "bidirectional"))
    )
    (net (code "62") (name "R4") (class "Default")
      (node (ref "R33") (pin "2") (pinfunction "2_2") (pintype "passive"))
      (node (ref "R5") (pin "1") (pinfunction "1_1") (pintype "passive"))
      (node (ref "U2") (pin "2") (pinfunction "PA1_2") (pintype "bidirectional"))
    )
    (net (code "63") (name "R5") (class "Default")
      (node (ref "R34") (pin "2") (pinfunction "2_2") (pintype "passive"))
      (node (ref "R6") (pin "1") (pinfunction "1_1") (pintype "passive"))
      (node (ref "U2") (pin "1") (pinfunction "PA0_1") (pintype "bidirectional"))
    )
    (net (code "64") (name "R6") (class "Default")
      (node (ref "R35") (pin "2") (pinfunction "2_2") (pintype "passive"))
      (node (ref "R7") (pin "1") (pinfunction "1_1") (pintype "passive"))
      (node (ref "U2") (pin "23") (pinfunction "PC14_23") (pintype "bidirectional"))
    )
    (net (code "65") (name "R7") (class "Default")
      (node (ref "R36") (pin "2") (pinfunction "2_2") (pintype "passive"))
      (node (ref "R8") (pin "1") (pinfunction "1_1") (pintype "passive"))
      (node (ref "U2") (pin "22") (pinfunction "PC13_22") (pintype "bidirectional"))
    )
    (net (code "66") (name "R8") (class "Default")
      (node (ref "R45") (pin "2") (pinfunction "2_2") (pintype "passive"))
      (node (ref "R9") (pin "1") (pinfunction "1_1") (pintype "passive"))
      (node (ref "U2") (pin "19") (pinfunction "PD7_19") (pintype "bidirectional"))
    )
    (net (code "67") (name "R9") (class "Default")
      (node (ref "R10") (pin "1") (pinfunction "1_1") (pintype "passive"))
      (node (ref "R46") (pin "2") (pinfunction "2_2") (pintype "passive"))
      (node (ref "U2") (pin "18") (pinfunction "PD6_18") (pintype "bidirectional"))
    )
    (net (code "68") (name "R10") (class "Default")
      (node (ref "R11") (pin "1") (pinfunction "1_1") (pintype "passive"))
      (node (ref "R47") (pin "2") (pinfunction "2_2") (pintype "passive"))
      (node (ref "U2") (pin "17") (pinfunction "PD5_17") (pintype "bidirectional"))
    )
    (net (code "69") (name "R11") (class "Default")
      (node (ref "R12") (pin "1") (pinfunction "1_1") (pintype "passive"))
      (node (ref "R48") (pin "2") (pinfunction "2_2") (pintype "passive"))
      (node (ref "U2") (pin "16") (pinfunction "PD4_16") (pintype "bidirectional"))
    )
    (net (code "70") (name "SWCLK") (class "Default")
      (node (ref "TC1") (pin "4") (pinfunction "S_4") (pintype "passive"))
      (node (ref "U2") (pin "25") (pinfunction "PF0_25") (pintype "bidirectional"))
    )
    (net (code "71") (name "SWDIO") (class "Default")
      (node (ref "TC1") (pin "2") (pinfunction "S_2") (pintype "passive"))
      (node (ref "U2") (pin "26") (pinfunction "PF1_26") (pintype "bidirectional"))
    )
    (net (code "72") (name "SWO") (class "Default")
      (node (ref "TC1") (pin "6") (pinfunction "S_6") (pintype "passive"))
      (node (ref "U2") (pin "27") (pinfunction "PF2_27") (pintype "bidirectional"))
    )
    (net (code "73") (name "VIN") (class "Default")
      (node (ref "C1") (pin "1") (pinfunction "C1_1") (pintype "passive"))
      (node (ref "C6") (pin "1") (pinfunction "C1_1") (pintype "passive"))
      (node (ref "CON10") (pin "P$2") (pinfunction "S_P$2") (pintype "passive"))
      (node (ref "CON11") (pin "P$2") (pinfunction "S_P$2") (pintype "passive"))
      (node (ref "CON12") (pin "P$2") (pinfunction "S_P$2") (pintype "passive"))
      (node (ref "CON13") (pin "P$2") (pinfunction "S_P$2") (pintype "passive"))
      (node (ref "CON14") (pin "P$2") (pinfunction "S_P$2") (pintype "passive"))
      (node (ref "CON3") (pin "P$2") (pinfunction "S_P$2") (pintype "passive"))
      (node (ref "CON4") (pin "P$2") (pinfunction "S_P$2") (pintype "passive"))
      (node (ref "CON5") (pin "P$2") (pinfunction "S_P$2") (pintype "passive"))
      (node (ref "CON6") (pin "P$2") (pinfunction "S_P$2") (pintype "passive"))
      (node (ref "CON7") (pin "P$2") (pinfunction "S_P$2") (pintype "passive"))
      (node (ref "CON8") (pin "P$2") (pinfunction "S_P$2") (pintype "passive"))
      (node (ref "CON9") (pin "P$2") (pinfunction "S_P$2") (pintype "passive"))
      (node (ref "D1") (pin "C") (pinfunction "C_C") (pintype "passive"))
      (node (ref "D10") (pin "A") (pinfunction "A_A") (pintype "passive"))
      (node (ref "D11") (pin "A") (pinfunction "A_A") (pintype "passive"))
      (node (ref "D12") (pin "A") (pinfunction "A_A") (pintype "passive"))
      (node (ref "D13") (pin "A") (pinfunction "A_A") (pintype "passive"))
      (node (ref "D14") (pin "C") (pinfunction "C_C") (pintype "passive"))
      (node (ref "D15") (pin "C") (pinfunction "C_C") (pintype "passive"))
      (node (ref "D16") (pin "C") (pinfunction "C_C") (pintype "passive"))
      (node (ref "D17") (pin "C") (pinfunction "C_C") (pintype "passive"))
      (node (ref "D18") (pin "A") (pinfunction "A_A") (pintype "passive"))
      (node (ref "D19") (pin "A") (pinfunction "A_A") (pintype "passive"))
      (node (ref "D2") (pin "A") (pinfunction "A_A") (pintype "passive"))
      (node (ref "D20") (pin "A") (pinfunction "A_A") (pintype "passive"))
      (node (ref "D21") (pin "A") (pinfunction "A_A") (pintype "passive"))
      (node (ref "D22") (pin "C") (pinfunction "C_C") (pintype "passive"))
      (node (ref "D23") (pin "C") (pinfunction "C_C") (pintype "passive"))
      (node (ref "D24") (pin "C") (pinfunction "C_C") (pintype "passive"))
      (node (ref "D25") (pin "C") (pinfunction "C_C") (pintype "passive"))
      (node (ref "D3") (pin "A") (pinfunction "A_A") (pintype "passive"))
      (node (ref "D4") (pin "A") (pinfunction "A_A") (pintype "passive"))
      (node (ref "D5") (pin "A") (pinfunction "A_A") (pintype "passive"))
      (node (ref "D6") (pin "C") (pinfunction "C_C") (pintype "passive"))
      (node (ref "D7") (pin "C") (pinfunction "C_C") (pintype "passive"))
      (node (ref "D8") (pin "C") (pinfunction "C_C") (pintype "passive"))
      (node (ref "D9") (pin "C") (pinfunction "C_C") (pintype "passive"))
      (node (ref "F1") (pin "1") (pinfunction "1_1") (pintype "passive"))
      (node (ref "R54") (pin "2") (pinfunction "2_2") (pintype "passive"))
      (node (ref "U1") (pin "3") (pinfunction "VIN_3") (pintype "bidirectional"))
    )
    (net (code "74") (name "VIN_VSENSE") (class "Default")
      (node (ref "C24") (pin "1") (pinfunction "C1_1") (pintype "passive"))
      (node (ref "R53") (pin "2") (pinfunction "2_2") (pintype "passive"))
      (node (ref "R54") (pin "1") (pinfunction "1_1") (pintype "passive"))
      (node (ref "U2") (pin "10") (pinfunction "PB11_10") (pintype "bidirectional"))
    )
    (net (code "75") (name "unconnected-(TC1F-S-Pad5)") (class "Default")
      (node (ref "TC1") (pin "5") (pinfunction "S_5") (pintype "passive"))
    )
    (net (code "76") (name "unconnected-(U2-PB13-Pad12)") (class "Default")
      (node (ref "U2") (pin "12") (pinfunction "PB13_12") (pintype "bidirectional"))
    )
    (net (code "77") (name "unconnected-(U2-PB14-Pad13)") (class "Default")
      (node (ref "U2") (pin "13") (pinfunction "PB14_13") (pintype "bidirectional"))
    )
    (net (code "78") (name "unconnected-(U2-PC0-Pad5)") (class "Default")
      (node (ref "U2") (pin "5") (pinfunction "PC0_5") (pintype "bidirectional"))
    )
    (net (code "79") (name "unconnected-(U2-PC15-Pad24)") (class "Default")
      (node (ref "U2") (pin "24") (pinfunction "PC15_24") (pintype "bidirectional"))
    )
    (net (code "80") (name "unconnected-(U2-PE10-Pad29)") (class "Default")
      (node (ref "U2") (pin "29") (pinfunction "PE10_29") (pintype "bidirectional"))
    )
    (net (code "81") (name "~{RESET}") (class "Default")
      (node (ref "R13") (pin "1") (pinfunction "1_1") (pintype "passive"))
      (node (ref "TC1") (pin "10") (pinfunction "S_10") (pintype "passive"))
      (node (ref "U2") (pin "9") (pinfunction "~{RESET}_9") (pintype "bidirectional"))
    )
  )
)
